# Temperature.net
KiCad netlist of a schematic drawn in Altium Designer
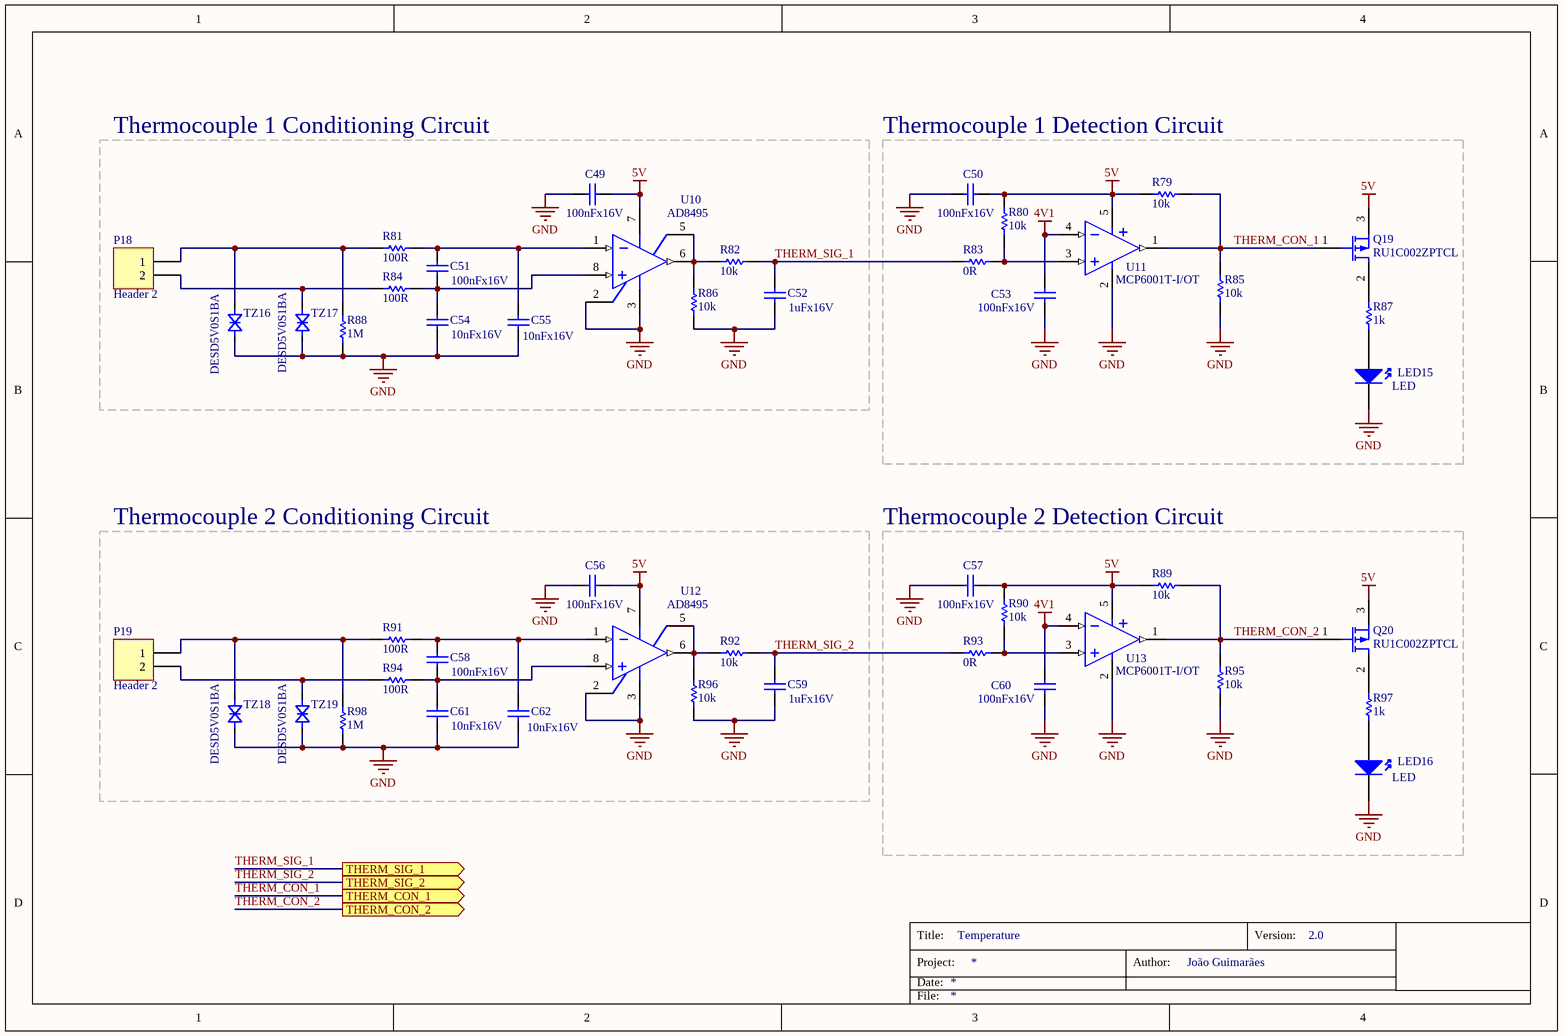
[diagram p0: Temperature.SchDoc]

(export (version "E")
  (design (tool "Eeschema 10.0.6"))
  (components
    (comp (ref "C49")
      (value "100nFx16V")
      (footprint "DISC-0805")
      (description "Capacitor")
      (libsource (lib "IntLib") (part "Cap"))
    )
    (comp (ref "C50")
      (value "100nFx16V")
      (footprint "DISC-0805")
      (description "Capacitor")
      (libsource (lib "IntLib") (part "Cap"))
    )
    (comp (ref "C51")
      (value "100nFx16V")
      (footprint "DISC-0805")
      (description "Capacitor")
      (libsource (lib "IntLib") (part "Cap"))
    )
    (comp (ref "C52")
      (value "1uFx16V")
      (footprint "DISC-0805")
      (description "Capacitor")
      (libsource (lib "IntLib") (part "Cap"))
    )
    (comp (ref "C53")
      (value "100nFx16V")
      (footprint "DISC-0805")
      (description "Capacitor")
      (libsource (lib "IntLib") (part "Cap"))
    )
    (comp (ref "C54")
      (value "10nFx16V")
      (footprint "DISC-0805")
      (description "Capacitor")
      (libsource (lib "IntLib") (part "Cap"))
    )
    (comp (ref "C55")
      (value "10nFx16V")
      (footprint "DISC-0805")
      (description "Capacitor")
      (libsource (lib "IntLib") (part "Cap"))
    )
    (comp (ref "C56")
      (value "100nFx16V")
      (footprint "DISC-0805")
      (description "Capacitor")
      (libsource (lib "IntLib") (part "Cap"))
    )
    (comp (ref "C57")
      (value "100nFx16V")
      (footprint "DISC-0805")
      (description "Capacitor")
      (libsource (lib "IntLib") (part "Cap"))
    )
    (comp (ref "C58")
      (value "100nFx16V")
      (footprint "DISC-0805")
      (description "Capacitor")
      (libsource (lib "IntLib") (part "Cap"))
    )
    (comp (ref "C59")
      (value "1uFx16V")
      (footprint "DISC-0805")
      (description "Capacitor")
      (libsource (lib "IntLib") (part "Cap"))
    )
    (comp (ref "C60")
      (value "100nFx16V")
      (footprint "DISC-0805")
      (description "Capacitor")
      (libsource (lib "IntLib") (part "Cap"))
    )
    (comp (ref "C61")
      (value "10nFx16V")
      (footprint "DISC-0805")
      (description "Capacitor")
      (libsource (lib "IntLib") (part "Cap"))
    )
    (comp (ref "C62")
      (value "10nFx16V")
      (footprint "DISC-0805")
      (description "Capacitor")
      (libsource (lib "IntLib") (part "Cap"))
    )
    (comp (ref "LED15") (value "LED") (footprint "DISC-LED-0.1-PTH") (libsource (lib "IntLib") (part "LED")))
    (comp (ref "LED16") (value "LED") (footprint "DISC-LED-0.1-PTH") (libsource (lib "IntLib") (part "LED")))
    (comp (ref "P18")
      (value "Header 2")
      (footprint "CON-FLEXWIRE-0.5MM2-1X2")
      (description "Header, 2-Pin")
      (fields (field (name "PUBLISHER") "Altium Limited"))
      (libsource (lib "IntLib") (part "Header 2"))
    )
    (comp (ref "P19")
      (value "Header 2")
      (footprint "CON-FLEXWIRE-0.5MM2-1X2")
      (description "Header, 2-Pin")
      (fields (field (name "PUBLISHER") "Altium Limited"))
      (libsource (lib "IntLib") (part "Header 2"))
    )
    (comp (ref "Q19")
      (value "RU1C002ZPTCL")
      (footprint "DISC-SOT-23")
      (description "P-Channel MOSFET")
      (libsource (lib "IntLib") (part "Transistor-PMOS"))
    )
    (comp (ref "Q20")
      (value "RU1C002ZPTCL")
      (footprint "DISC-SOT-23")
      (description "P-Channel MOSFET")
      (libsource (lib "IntLib") (part "Transistor-PMOS"))
    )
    (comp (ref "R79")
      (value "10k")
      (footprint "DISC-0805")
      (description "Resistor")
      (libsource (lib "IntLib") (part "Res"))
    )
    (comp (ref "R80")
      (value "10k")
      (footprint "DISC-0805")
      (description "Resistor")
      (libsource (lib "IntLib") (part "Res"))
    )
    (comp (ref "R81")
      (value "100R")
      (footprint "DISC-0805")
      (description "Resistor")
      (libsource (lib "IntLib") (part "Res"))
    )
    (comp (ref "R82")
      (value "10k")
      (footprint "DISC-0805")
      (description "Resistor")
      (libsource (lib "IntLib") (part "Res"))
    )
    (comp (ref "R83")
      (value "0R")
      (footprint "DISC-0805")
      (description "Resistor")
      (libsource (lib "IntLib") (part "Res"))
    )
    (comp (ref "R84")
      (value "100R")
      (footprint "DISC-0805")
      (description "Resistor")
      (libsource (lib "IntLib") (part "Res"))
    )
    (comp (ref "R85")
      (value "10k")
      (footprint "DISC-0805")
      (description "Resistor")
      (libsource (lib "IntLib") (part "Res"))
    )
    (comp (ref "R86")
      (value "10k")
      (footprint "DISC-0805")
      (description "Resistor")
      (libsource (lib "IntLib") (part "Res"))
    )
    (comp (ref "R87")
      (value "1k")
      (footprint "DISC-0805")
      (description "Resistor")
      (libsource (lib "IntLib") (part "Res"))
    )
    (comp (ref "R88")
      (value "1M")
      (footprint "DISC-0805")
      (description "Resistor")
      (libsource (lib "IntLib") (part "Res"))
    )
    (comp (ref "R89")
      (value "10k")
      (footprint "DISC-0805")
      (description "Resistor")
      (libsource (lib "IntLib") (part "Res"))
    )
    (comp (ref "R90")
      (value "10k")
      (footprint "DISC-0805")
      (description "Resistor")
      (libsource (lib "IntLib") (part "Res"))
    )
    (comp (ref "R91")
      (value "100R")
      (footprint "DISC-0805")
      (description "Resistor")
      (libsource (lib "IntLib") (part "Res"))
    )
    (comp (ref "R92")
      (value "10k")
      (footprint "DISC-0805")
      (description "Resistor")
      (libsource (lib "IntLib") (part "Res"))
    )
    (comp (ref "R93")
      (value "0R")
      (footprint "DISC-0805")
      (description "Resistor")
      (libsource (lib "IntLib") (part "Res"))
    )
    (comp (ref "R94")
      (value "100R")
      (footprint "DISC-0805")
      (description "Resistor")
      (libsource (lib "IntLib") (part "Res"))
    )
    (comp (ref "R95")
      (value "10k")
      (footprint "DISC-0805")
      (description "Resistor")
      (libsource (lib "IntLib") (part "Res"))
    )
    (comp (ref "R96")
      (value "10k")
      (footprint "DISC-0805")
      (description "Resistor")
      (libsource (lib "IntLib") (part "Res"))
    )
    (comp (ref "R97")
      (value "1k")
      (footprint "DISC-0805")
      (description "Resistor")
      (libsource (lib "IntLib") (part "Res"))
    )
    (comp (ref "R98")
      (value "1M")
      (footprint "DISC-0805")
      (description "Resistor")
      (libsource (lib "IntLib") (part "Res"))
    )
    (comp (ref "TZ16")
      (value "DESD5V0S1BA")
      (footprint "DISC-SOD-323")
      (description "TVZ-Bi-Directional")
      (libsource (lib "IntLib") (part "TVZ-Bi-Directional"))
    )
    (comp (ref "TZ17")
      (value "DESD5V0S1BA")
      (footprint "DISC-SOD-323")
      (description "TVZ-Bi-Directional")
      (libsource (lib "IntLib") (part "TVZ-Bi-Directional"))
    )
    (comp (ref "TZ18")
      (value "DESD5V0S1BA")
      (footprint "DISC-SOD-323")
      (description "TVZ-Bi-Directional")
      (libsource (lib "IntLib") (part "TVZ-Bi-Directional"))
    )
    (comp (ref "TZ19")
      (value "DESD5V0S1BA")
      (footprint "DISC-SOD-323")
      (description "TVZ-Bi-Directional")
      (libsource (lib "IntLib") (part "TVZ-Bi-Directional"))
    )
    (comp (ref "U10")
      (value "AD8495")
      (footprint "CI-MSOP-8")
      (description "Precision Type K Thermocouple Amplifier with Cold Junction Compensation")
      (libsource (lib "IntLib") (part "AD8495"))
    )
    (comp (ref "U11")
      (value "MCP6001T-I/OT")
      (footprint "CI-SOT-23-5")
      (description "Operational Amplifiers - Op Amps Single 1.8V 1MHz")
      (libsource (lib "IntLib") (part "MCP6001T-I/OT"))
    )
    (comp (ref "U12")
      (value "AD8495")
      (footprint "CI-MSOP-8")
      (description "Precision Type K Thermocouple Amplifier with Cold Junction Compensation")
      (libsource (lib "IntLib") (part "AD8495"))
    )
    (comp (ref "U13")
      (value "MCP6001T-I/OT")
      (footprint "CI-SOT-23-5")
      (description "Operational Amplifiers - Op Amps Single 1.8V 1MHz")
      (libsource (lib "IntLib") (part "MCP6001T-I/OT"))
    )
  )
  (nets
    (net (code "1") (name "/THERM_CON_1") (class "Default")
      (node (ref "Q19") (pin "1") (pinfunction "G_1") (pintype "passive"))
      (node (ref "R79") (pin "2") (pinfunction "2_2") (pintype "passive"))
      (node (ref "R85") (pin "1") (pinfunction "1_1") (pintype "passive"))
      (node (ref "U11") (pin "1") (pinfunction "Out_1") (pintype "output"))
    )
    (net (code "2") (name "/THERM_CON_2") (class "Default")
      (node (ref "Q20") (pin "1") (pinfunction "G_1") (pintype "passive"))
      (node (ref "R89") (pin "2") (pinfunction "2_2") (pintype "passive"))
      (node (ref "R95") (pin "1") (pinfunction "1_1") (pintype "passive"))
      (node (ref "U13") (pin "1") (pinfunction "Out_1") (pintype "output"))
    )
    (net (code "3") (name "/THERM_SIG_1") (class "Default")
      (node (ref "C52") (pin "2") (pinfunction "2_2") (pintype "passive"))
      (node (ref "R82") (pin "2") (pinfunction "2_2") (pintype "passive"))
      (node (ref "R83") (pin "1") (pinfunction "1_1") (pintype "passive"))
    )
    (net (code "4") (name "/THERM_SIG_2") (class "Default")
      (node (ref "C59") (pin "2") (pinfunction "2_2") (pintype "passive"))
      (node (ref "R92") (pin "2") (pinfunction "2_2") (pintype "passive"))
      (node (ref "R93") (pin "1") (pinfunction "1_1") (pintype "passive"))
    )
    (net (code "5") (name "4V1") (class "Default")
      (node (ref "C53") (pin "2") (pinfunction "2_2") (pintype "passive"))
      (node (ref "C60") (pin "2") (pinfunction "2_2") (pintype "passive"))
      (node (ref "U11") (pin "4") (pinfunction "IN-_4") (pintype "input"))
      (node (ref "U13") (pin "4") (pinfunction "IN-_4") (pintype "input"))
    )
    (net (code "6") (name "5V") (class "Default")
      (node (ref "C49") (pin "1") (pinfunction "1_1") (pintype "passive"))
      (node (ref "C50") (pin "2") (pinfunction "2_2") (pintype "passive"))
      (node (ref "C56") (pin "1") (pinfunction "1_1") (pintype "passive"))
      (node (ref "C57") (pin "2") (pinfunction "2_2") (pintype "passive"))
      (node (ref "Q19") (pin "3") (pinfunction "S_3") (pintype "passive"))
      (node (ref "Q20") (pin "3") (pinfunction "S_3") (pintype "passive"))
      (node (ref "R79") (pin "1") (pinfunction "1_1") (pintype "passive"))
      (node (ref "R80") (pin "1") (pinfunction "1_1") (pintype "passive"))
      (node (ref "R89") (pin "1") (pinfunction "1_1") (pintype "passive"))
      (node (ref "R90") (pin "1") (pinfunction "1_1") (pintype "passive"))
      (node (ref "U10") (pin "7") (pinfunction "V+_7") (pintype "power_in"))
      (node (ref "U11") (pin "5") (pinfunction "V+_5") (pintype "power_in"))
      (node (ref "U12") (pin "7") (pinfunction "V+_7") (pintype "power_in"))
      (node (ref "U13") (pin "5") (pinfunction "V+_5") (pintype "power_in"))
    )
    (net (code "7") (name "GND") (class "Default")
      (node (ref "C49") (pin "2") (pinfunction "2_2") (pintype "passive"))
      (node (ref "C50") (pin "1") (pinfunction "1_1") (pintype "passive"))
      (node (ref "C52") (pin "1") (pinfunction "1_1") (pintype "passive"))
      (node (ref "C53") (pin "1") (pinfunction "1_1") (pintype "passive"))
      (node (ref "C54") (pin "1") (pinfunction "1_1") (pintype "passive"))
      (node (ref "C55") (pin "1") (pinfunction "1_1") (pintype "passive"))
      (node (ref "C56") (pin "2") (pinfunction "2_2") (pintype "passive"))
      (node (ref "C57") (pin "1") (pinfunction "1_1") (pintype "passive"))
      (node (ref "C59") (pin "1") (pinfunction "1_1") (pintype "passive"))
      (node (ref "C60") (pin "1") (pinfunction "1_1") (pintype "passive"))
      (node (ref "C61") (pin "1") (pinfunction "1_1") (pintype "passive"))
      (node (ref "C62") (pin "1") (pinfunction "1_1") (pintype "passive"))
      (node (ref "LED15") (pin "2") (pinfunction "K_2") (pintype "passive"))
      (node (ref "LED16") (pin "2") (pinfunction "K_2") (pintype "passive"))
      (node (ref "R85") (pin "2") (pinfunction "2_2") (pintype "passive"))
      (node (ref "R86") (pin "2") (pinfunction "2_2") (pintype "passive"))
      (node (ref "R88") (pin "1") (pinfunction "1_1") (pintype "passive"))
      (node (ref "R95") (pin "2") (pinfunction "2_2") (pintype "passive"))
      (node (ref "R96") (pin "2") (pinfunction "2_2") (pintype "passive"))
      (node (ref "R98") (pin "1") (pinfunction "1_1") (pintype "passive"))
      (node (ref "TZ16") (pin "1") (pinfunction "A_1") (pintype "passive"))
      (node (ref "TZ17") (pin "1") (pinfunction "A_1") (pintype "passive"))
      (node (ref "TZ18") (pin "1") (pinfunction "A_1") (pintype "passive"))
      (node (ref "TZ19") (pin "1") (pinfunction "A_1") (pintype "passive"))
      (node (ref "U10") (pin "2") (pinfunction "REF_2") (pintype "passive"))
      (node (ref "U10") (pin "3") (pinfunction "V-_3") (pintype "power_in"))
      (node (ref "U11") (pin "2") (pinfunction "V-_2") (pintype "power_in"))
      (node (ref "U12") (pin "2") (pinfunction "REF_2") (pintype "passive"))
      (node (ref "U12") (pin "3") (pinfunction "V-_3") (pintype "power_in"))
      (node (ref "U13") (pin "2") (pinfunction "V-_2") (pintype "power_in"))
    )
    (net (code "8") (name "Net-(LED15-A)") (class "Default")
      (node (ref "LED15") (pin "1") (pinfunction "A_1") (pintype "passive"))
      (node (ref "R87") (pin "1") (pinfunction "1_1") (pintype "passive"))
    )
    (net (code "9") (name "Net-(LED16-A)") (class "Default")
      (node (ref "LED16") (pin "1") (pinfunction "A_1") (pintype "passive"))
      (node (ref "R97") (pin "1") (pinfunction "1_1") (pintype "passive"))
    )
    (net (code "10") (name "Net-(Q19-D)") (class "Default")
      (node (ref "Q19") (pin "2") (pinfunction "D_2") (pintype "passive"))
      (node (ref "R87") (pin "2") (pinfunction "2_2") (pintype "passive"))
    )
    (net (code "11") (name "Net-(Q20-D)") (class "Default")
      (node (ref "Q20") (pin "2") (pinfunction "D_2") (pintype "passive"))
      (node (ref "R97") (pin "2") (pinfunction "2_2") (pintype "passive"))
    )
    (net (code "12") (name "Net-(TZ16-K)") (class "Default")
      (node (ref "P18") (pin "1") (pinfunction "1_1") (pintype "passive"))
      (node (ref "R81") (pin "2") (pinfunction "2_2") (pintype "passive"))
      (node (ref "R88") (pin "2") (pinfunction "2_2") (pintype "passive"))
      (node (ref "TZ16") (pin "2") (pinfunction "K_2") (pintype "passive"))
    )
    (net (code "13") (name "Net-(TZ17-K)") (class "Default")
      (node (ref "P18") (pin "2") (pinfunction "2_2") (pintype "passive"))
      (node (ref "R84") (pin "2") (pinfunction "2_2") (pintype "passive"))
      (node (ref "TZ17") (pin "2") (pinfunction "K_2") (pintype "passive"))
    )
    (net (code "14") (name "Net-(TZ18-K)") (class "Default")
      (node (ref "P19") (pin "1") (pinfunction "1_1") (pintype "passive"))
      (node (ref "R91") (pin "2") (pinfunction "2_2") (pintype "passive"))
      (node (ref "R98") (pin "2") (pinfunction "2_2") (pintype "passive"))
      (node (ref "TZ18") (pin "2") (pinfunction "K_2") (pintype "passive"))
    )
    (net (code "15") (name "Net-(TZ19-K)") (class "Default")
      (node (ref "P19") (pin "2") (pinfunction "2_2") (pintype "passive"))
      (node (ref "R94") (pin "2") (pinfunction "2_2") (pintype "passive"))
      (node (ref "TZ19") (pin "2") (pinfunction "K_2") (pintype "passive"))
    )
    (net (code "16") (name "Net-(U10-IN+)") (class "Default")
      (node (ref "C51") (pin "1") (pinfunction "1_1") (pintype "passive"))
      (node (ref "C54") (pin "2") (pinfunction "2_2") (pintype "passive"))
      (node (ref "R84") (pin "1") (pinfunction "1_1") (pintype "passive"))
      (node (ref "U10") (pin "8") (pinfunction "IN+_8") (pintype "input"))
    )
    (net (code "17") (name "Net-(U10-IN-)") (class "Default")
      (node (ref "C51") (pin "2") (pinfunction "2_2") (pintype "passive"))
      (node (ref "C55") (pin "2") (pinfunction "2_2") (pintype "passive"))
      (node (ref "R81") (pin "1") (pinfunction "1_1") (pintype "passive"))
      (node (ref "U10") (pin "1") (pinfunction "IN-_1") (pintype "input"))
    )
    (net (code "18") (name "Net-(U10-OUT)") (class "Default")
      (node (ref "R82") (pin "1") (pinfunction "1_1") (pintype "passive"))
      (node (ref "R86") (pin "1") (pinfunction "1_1") (pintype "passive"))
      (node (ref "U10") (pin "5") (pinfunction "SENSE_5") (pintype "passive"))
      (node (ref "U10") (pin "6") (pinfunction "OUT_6") (pintype "output"))
    )
    (net (code "19") (name "Net-(U11-IN+)") (class "Default")
      (node (ref "R80") (pin "2") (pinfunction "2_2") (pintype "passive"))
      (node (ref "R83") (pin "2") (pinfunction "2_2") (pintype "passive"))
      (node (ref "U11") (pin "3") (pinfunction "IN+_3") (pintype "input"))
    )
    (net (code "20") (name "Net-(U12-IN+)") (class "Default")
      (node (ref "C58") (pin "1") (pinfunction "1_1") (pintype "passive"))
      (node (ref "C61") (pin "2") (pinfunction "2_2") (pintype "passive"))
      (node (ref "R94") (pin "1") (pinfunction "1_1") (pintype "passive"))
      (node (ref "U12") (pin "8") (pinfunction "IN+_8") (pintype "input"))
    )
    (net (code "21") (name "Net-(U12-IN-)") (class "Default")
      (node (ref "C58") (pin "2") (pinfunction "2_2") (pintype "passive"))
      (node (ref "C62") (pin "2") (pinfunction "2_2") (pintype "passive"))
      (node (ref "R91") (pin "1") (pinfunction "1_1") (pintype "passive"))
      (node (ref "U12") (pin "1") (pinfunction "IN-_1") (pintype "input"))
    )
    (net (code "22") (name "Net-(U12-OUT)") (class "Default")
      (node (ref "R92") (pin "1") (pinfunction "1_1") (pintype "passive"))
      (node (ref "R96") (pin "1") (pinfunction "1_1") (pintype "passive"))
      (node (ref "U12") (pin "5") (pinfunction "SENSE_5") (pintype "passive"))
      (node (ref "U12") (pin "6") (pinfunction "OUT_6") (pintype "output"))
    )
    (net (code "23") (name "Net-(U13-IN+)") (class "Default")
      (node (ref "R90") (pin "2") (pinfunction "2_2") (pintype "passive"))
      (node (ref "R93") (pin "2") (pinfunction "2_2") (pintype "passive"))
      (node (ref "U13") (pin "3") (pinfunction "IN+_3") (pintype "input"))
    )
  )
)
